# EasyCheck_CHIP_REV1.net
KiCad netlist of a schematic drawn in EAGLE
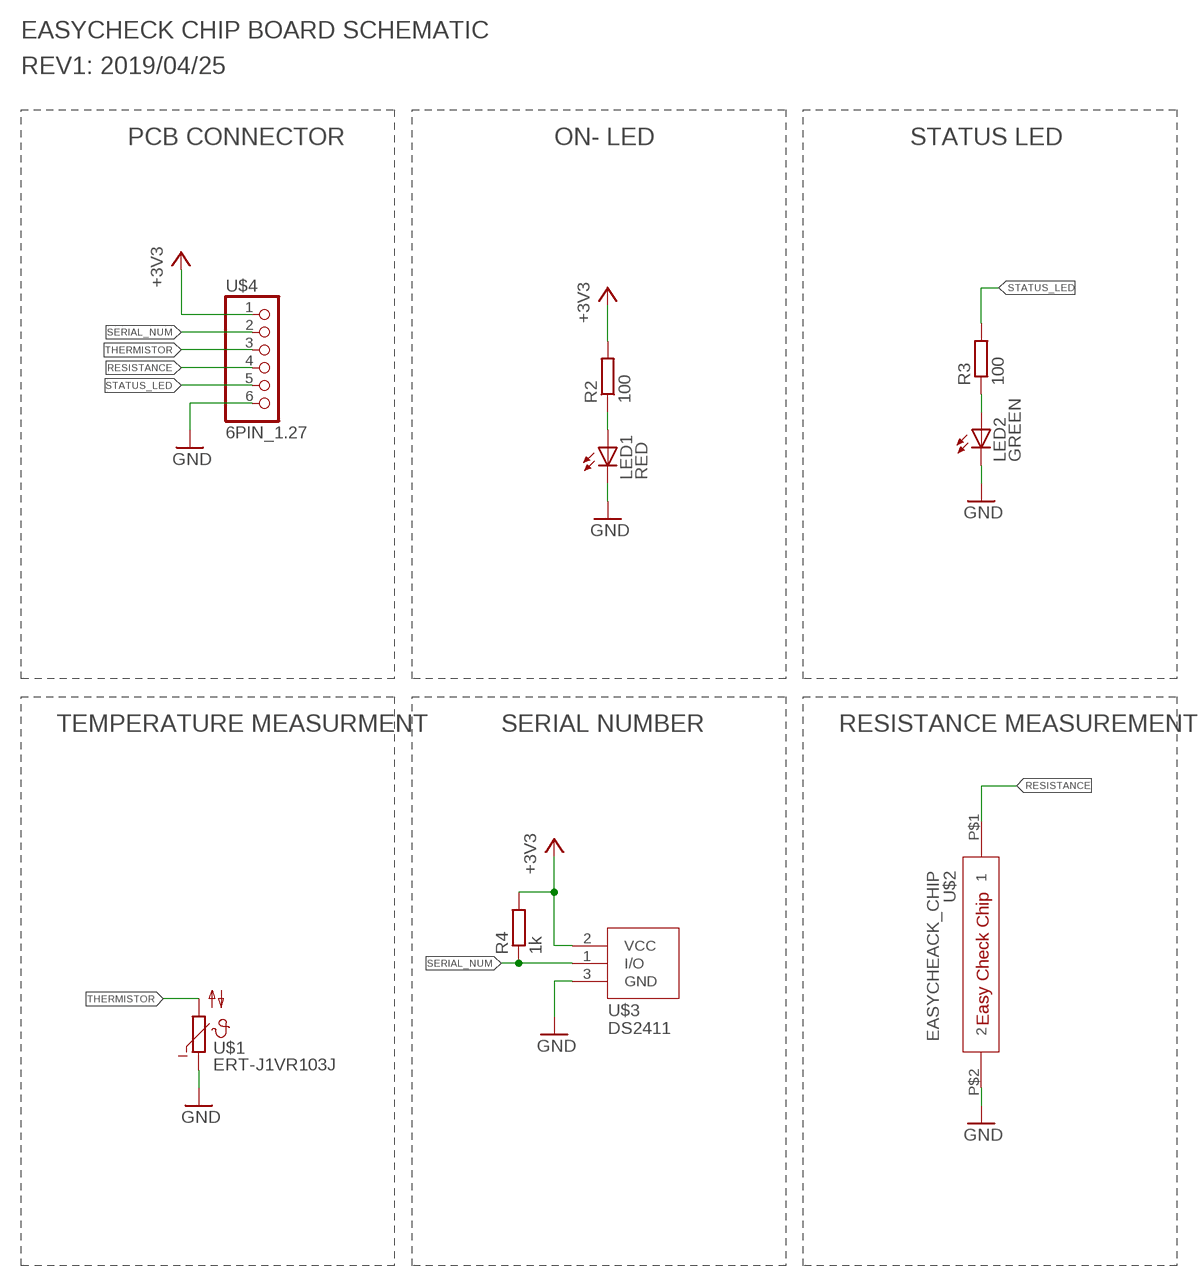
[diagram p0: schematic, sheet 1]

(export (version "E")
  (design (tool "Eeschema 10.0.6"))
  (components
    (comp (ref "LED1")
      (value "RED")
      (footprint "eagle-import:CHIPLED_0603")
      (libsource (lib "eagle-import") (part "LEDCHIPLED_0603"))
    )
    (comp (ref "LED2")
      (value "GREEN")
      (footprint "eagle-import:CHIPLED_0603")
      (libsource (lib "eagle-import") (part "LEDCHIPLED_0603"))
    )
    (comp (ref "R2")
      (value "100")
      (footprint "eagle-import:R0402")
      (libsource (lib "eagle-import") (part "R-EU_R0402"))
    )
    (comp (ref "R3")
      (value "100")
      (footprint "eagle-import:R0402")
      (libsource (lib "eagle-import") (part "R-EU_R0402"))
    )
    (comp (ref "R4")
      (value "1k")
      (footprint "eagle-import:R0402")
      (libsource (lib "eagle-import") (part "R-EU_R0402"))
    )
    (comp (ref "U$1")
      (value "ERT-J1VR103J")
      (footprint "eagle-import:C0603K")
      (libsource (lib "eagle-import") (part "NTC_SMD"))
    )
    (comp (ref "U$2")
      (value "EASYCHEACK_CHIP")
      (footprint "eagle-import:EASYCHECK_CHIP")
      (libsource (lib "eagle-import") (part "EASYCHEACK_CHIP"))
    )
    (comp (ref "U$3")
      (value "DS2411")
      (footprint "eagle-import:SOT23")
      (libsource (lib "eagle-import") (part "DS2411"))
    )
    (comp (ref "U$4")
      (value "6PIN_1.27")
      (footprint "eagle-import:6X1PIN_1.27")
      (libsource (lib "eagle-import") (part "6PIN_1.27"))
    )
  )
  (nets
    (net (code "1") (name "+3V3") (class "Default")
      (node (ref "R2") (pin "2") (pinfunction "2_2") (pintype "passive"))
      (node (ref "R4") (pin "2") (pinfunction "2_2") (pintype "passive"))
      (node (ref "U$3") (pin "2") (pinfunction "VCC_2") (pintype "bidirectional"))
      (node (ref "U$4") (pin "1") (pinfunction "1_1") (pintype "passive"))
    )
    (net (code "2") (name "GND") (class "Default")
      (node (ref "LED1") (pin "C") (pinfunction "C_C") (pintype "passive"))
      (node (ref "LED2") (pin "C") (pinfunction "C_C") (pintype "passive"))
      (node (ref "U$1") (pin "1") (pinfunction "1_1") (pintype "passive"))
      (node (ref "U$2") (pin "P$2") (pinfunction "2_P$2") (pintype "bidirectional"))
      (node (ref "U$3") (pin "3") (pinfunction "GND_3") (pintype "bidirectional"))
      (node (ref "U$4") (pin "6") (pinfunction "6_6") (pintype "passive"))
    )
    (net (code "3") (name "Net-(LED1-PadA)") (class "Default")
      (node (ref "LED1") (pin "A") (pinfunction "A_A") (pintype "passive"))
      (node (ref "R2") (pin "1") (pinfunction "1_1") (pintype "passive"))
    )
    (net (code "4") (name "Net-(LED2-PadA)") (class "Default")
      (node (ref "LED2") (pin "A") (pinfunction "A_A") (pintype "passive"))
      (node (ref "R3") (pin "1") (pinfunction "1_1") (pintype "passive"))
    )
    (net (code "5") (name "RESISTANCE") (class "Default")
      (node (ref "U$2") (pin "P$1") (pinfunction "1_P$1") (pintype "bidirectional"))
      (node (ref "U$4") (pin "4") (pinfunction "4_4") (pintype "passive"))
    )
    (net (code "6") (name "SERIAL_NUM") (class "Default")
      (node (ref "R4") (pin "1") (pinfunction "1_1") (pintype "passive"))
      (node (ref "U$3") (pin "1") (pinfunction "I/O_1") (pintype "bidirectional"))
      (node (ref "U$4") (pin "2") (pinfunction "2_2") (pintype "passive"))
    )
    (net (code "7") (name "STATUS_LED") (class "Default")
      (node (ref "R3") (pin "2") (pinfunction "2_2") (pintype "passive"))
      (node (ref "U$4") (pin "5") (pinfunction "5_5") (pintype "passive"))
    )
    (net (code "8") (name "THERMISTOR") (class "Default")
      (node (ref "U$1") (pin "2") (pinfunction "2_2") (pintype "passive"))
      (node (ref "U$4") (pin "3") (pinfunction "3_3") (pintype "passive"))
    )
  )
)
